# FPGA_Banks_67_68_DDR32.net
KiCad netlist of a schematic drawn in Altium Designer
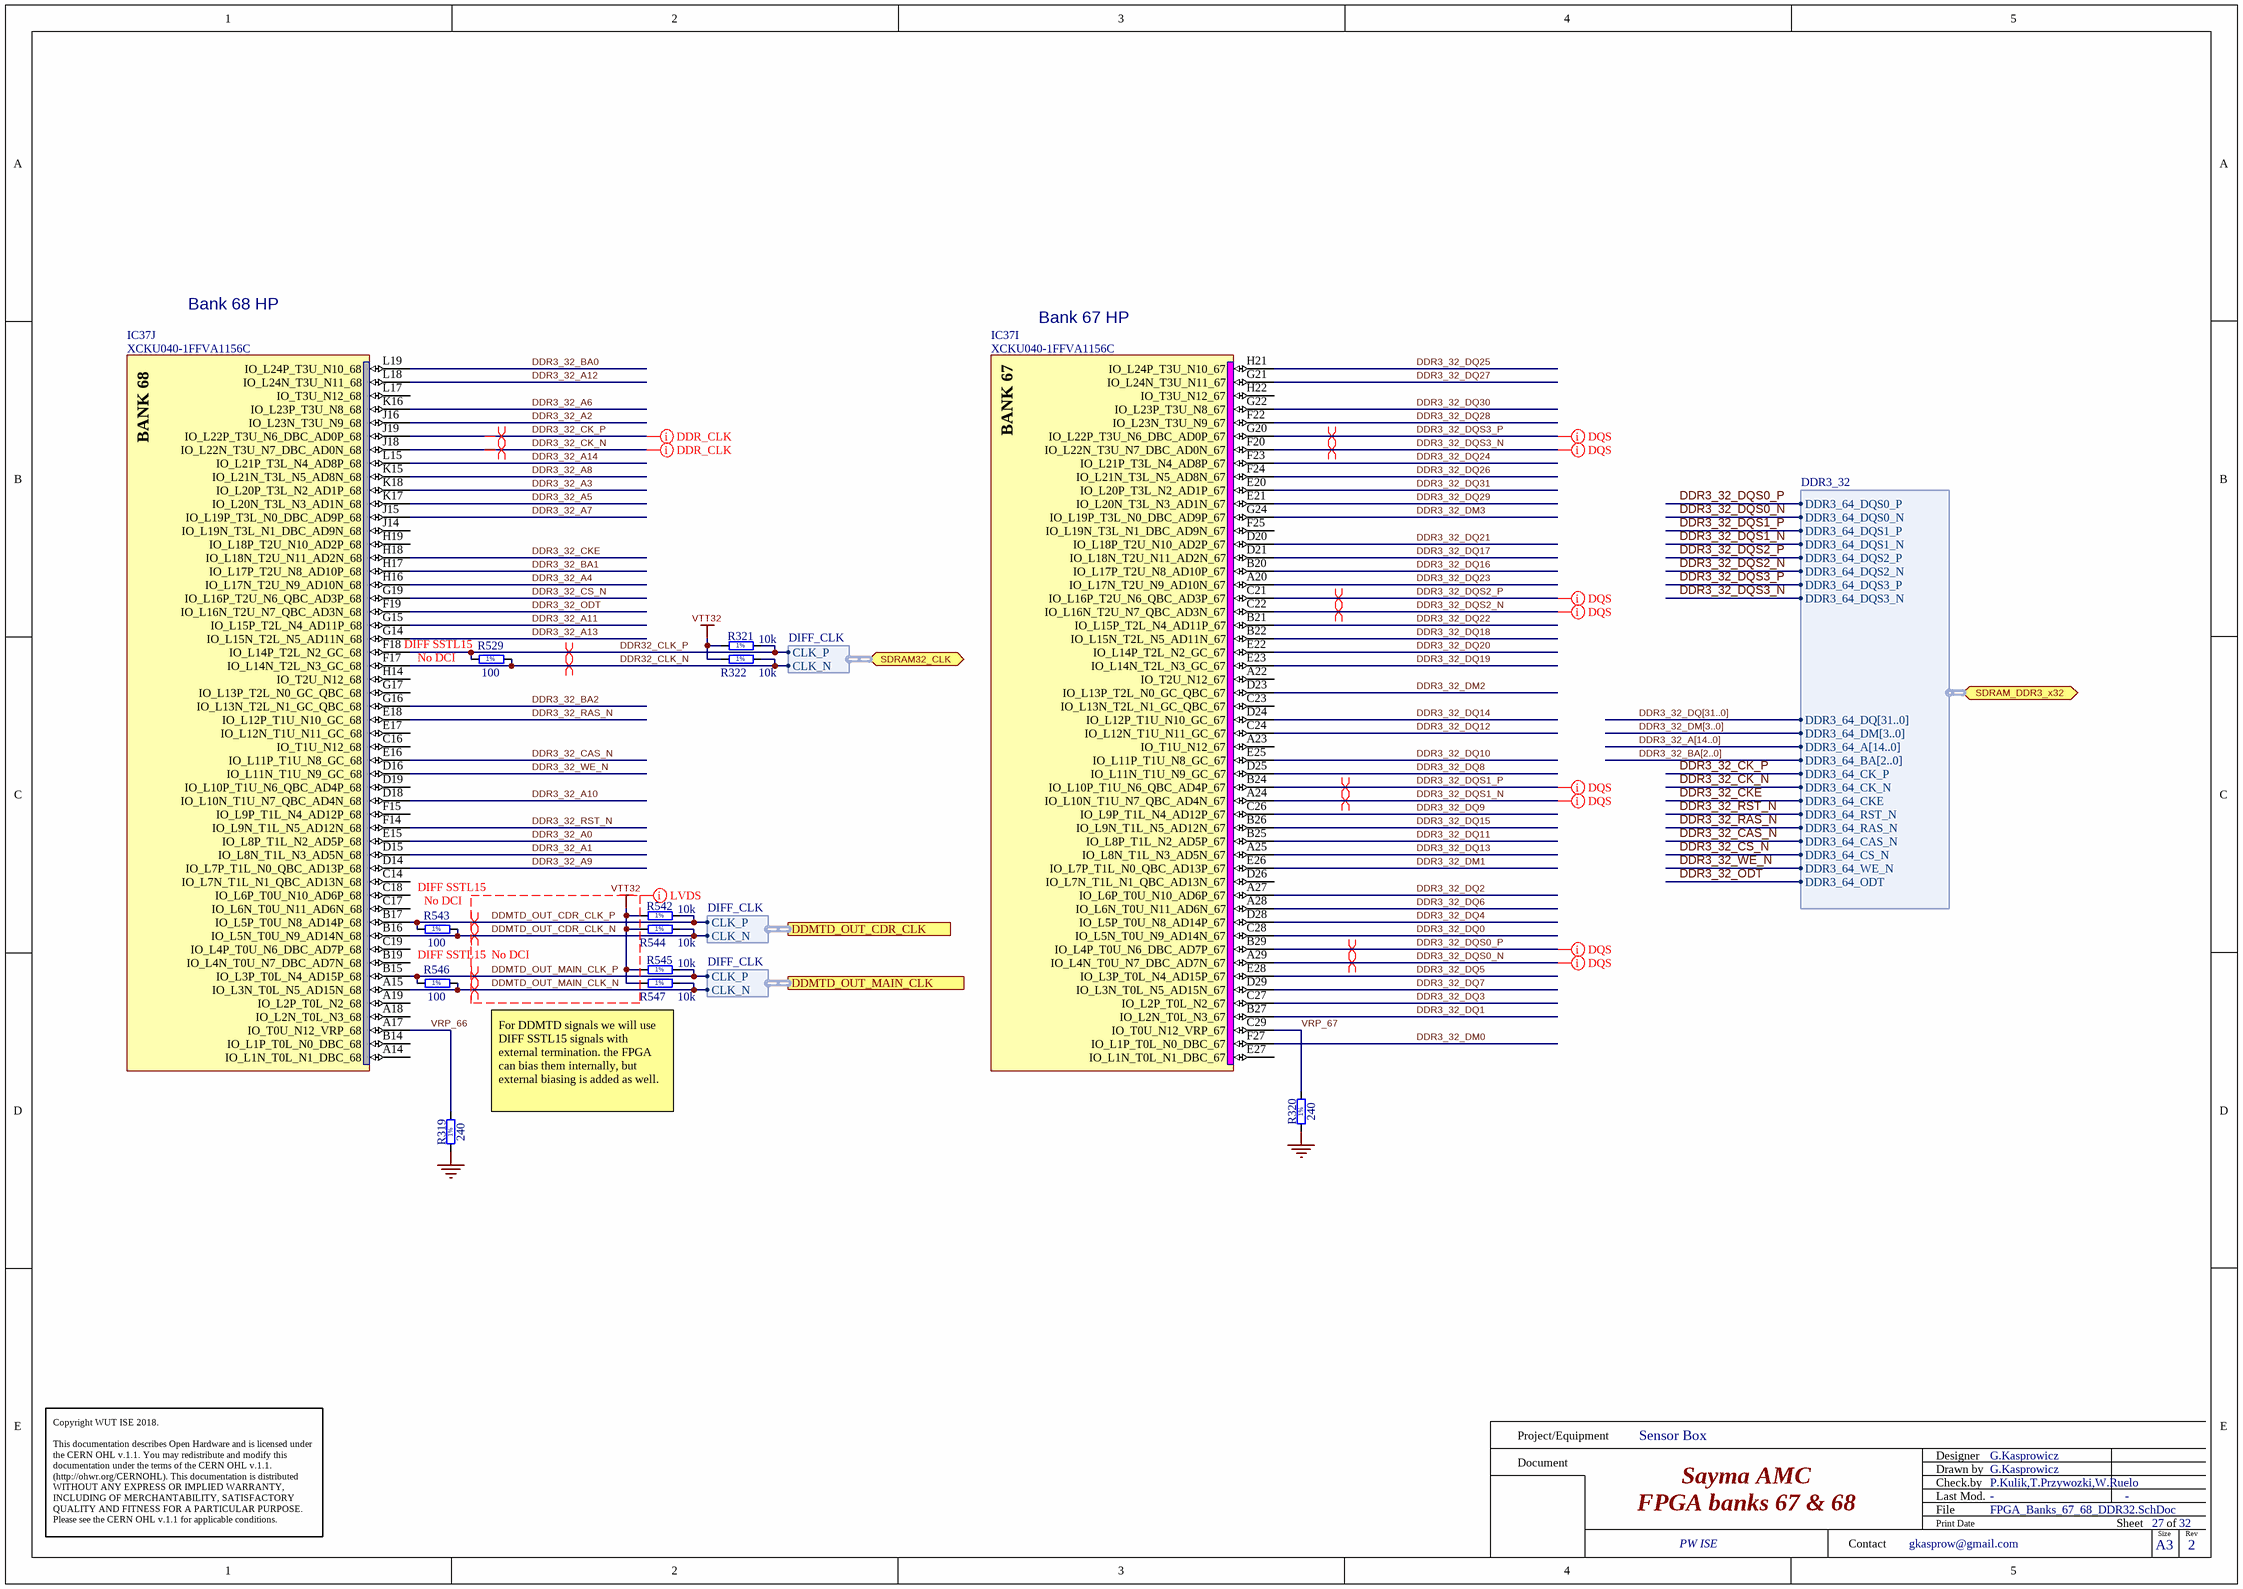
[diagram p0: FPGA_Banks_67_68_DDR32.SchDoc]

(export (version "E")
  (design (tool "Eeschema 10.0.6"))
  (components
    (comp (ref "IC37")
      (value "XCKU040-1FFVA1156C")
      (footprint "BGA1156C100P34X34_3500X3500X350")
      (description "Kintex UltraScale FPGA, 520 I/O, 530K Cells, 1156-Ball BGA, Speed Grade 1, Commercial Grade")
      (fields (field (name "MANUFACTURER") "XILINX") (field (name "AUTHOR") "CERN DEM CA"))
      (libsource (lib "ICs And Semiconductors") (part "XCKU040-1FFVA1156C"))
    )
    (comp (ref "R319")
      (value "240")
      (footprint "RESC1005X40N")
      (description "Resistor - 1%")
      (fields
        (field (name "MANUFACTURER PART NUMBER") "R0402_240R_1%_0.0625W_100PPM")
        (field (name "MANUFACTURER") "GENERIC")
        (field (name "AUTHOR") "CERN DEM JLC")
      )
      (libsource (lib "Resistors") (part "Resistor - 1%"))
    )
    (comp (ref "R320")
      (value "240")
      (footprint "RESC1005X40N")
      (description "Resistor - 1%")
      (fields
        (field (name "MANUFACTURER PART NUMBER") "R0402_240R_1%_0.0625W_100PPM")
        (field (name "MANUFACTURER") "GENERIC")
        (field (name "AUTHOR") "CERN DEM JLC")
      )
      (libsource (lib "Resistors") (part "Resistor - 1%"))
    )
    (comp (ref "R321")
      (value "10k")
      (footprint "RESC1005X40N")
      (description "Resistor - 1%")
      (fields
        (field (name "MANUFACTURER PART NUMBER") "R0402_10K_1%_0.0625W_100PPM")
        (field (name "MANUFACTURER") "GENERIC")
        (field (name "AUTHOR") "CERN DEM JLC")
      )
      (libsource (lib "Resistors") (part "Resistor - 1%"))
    )
    (comp (ref "R322")
      (value "10k")
      (footprint "RESC1005X40N")
      (description "Resistor - 1%")
      (fields
        (field (name "MANUFACTURER PART NUMBER") "R0402_10K_1%_0.0625W_100PPM")
        (field (name "MANUFACTURER") "GENERIC")
        (field (name "AUTHOR") "CERN DEM JLC")
      )
      (libsource (lib "Resistors") (part "Resistor - 1%"))
    )
    (comp (ref "R529")
      (value "100")
      (footprint "RESC0603X28N")
      (description "Resistor - 1%")
      (fields
        (field (name "MANUFACTURER PART NUMBER") "R0201_100R_1%_0.05W_200PPM")
        (field (name "MANUFACTURER") "GENERIC")
        (field (name "AUTHOR") "CERN DEM JLC")
      )
      (libsource (lib "Resistors") (part "Resistor - 1%"))
    )
    (comp (ref "R542")
      (value "10k")
      (footprint "RESC1005X40N")
      (description "Resistor - 1%")
      (fields
        (field (name "MANUFACTURER PART NUMBER") "R0402_10K_1%_0.0625W_100PPM")
        (field (name "MANUFACTURER") "GENERIC")
        (field (name "AUTHOR") "CERN DEM JLC")
      )
      (libsource (lib "Resistors") (part "Resistor - 1%"))
    )
    (comp (ref "R543")
      (value "100")
      (footprint "RESC0603X28N")
      (description "Resistor - 1%")
      (fields
        (field (name "MANUFACTURER PART NUMBER") "R0201_100R_1%_0.05W_200PPM")
        (field (name "MANUFACTURER") "GENERIC")
        (field (name "AUTHOR") "CERN DEM JLC")
      )
      (libsource (lib "Resistors") (part "Resistor - 1%"))
    )
    (comp (ref "R544")
      (value "10k")
      (footprint "RESC1005X40N")
      (description "Resistor - 1%")
      (fields
        (field (name "MANUFACTURER PART NUMBER") "R0402_10K_1%_0.0625W_100PPM")
        (field (name "MANUFACTURER") "GENERIC")
        (field (name "AUTHOR") "CERN DEM JLC")
      )
      (libsource (lib "Resistors") (part "Resistor - 1%"))
    )
    (comp (ref "R545")
      (value "10k")
      (footprint "RESC1005X40N")
      (description "Resistor - 1%")
      (fields
        (field (name "MANUFACTURER PART NUMBER") "R0402_10K_1%_0.0625W_100PPM")
        (field (name "MANUFACTURER") "GENERIC")
        (field (name "AUTHOR") "CERN DEM JLC")
      )
      (libsource (lib "Resistors") (part "Resistor - 1%"))
    )
    (comp (ref "R546")
      (value "100")
      (footprint "RESC0603X28N")
      (description "Resistor - 1%")
      (fields
        (field (name "MANUFACTURER PART NUMBER") "R0201_100R_1%_0.05W_200PPM")
        (field (name "MANUFACTURER") "GENERIC")
        (field (name "AUTHOR") "CERN DEM JLC")
      )
      (libsource (lib "Resistors") (part "Resistor - 1%"))
    )
    (comp (ref "R547")
      (value "10k")
      (footprint "RESC1005X40N")
      (description "Resistor - 1%")
      (fields
        (field (name "MANUFACTURER PART NUMBER") "R0402_10K_1%_0.0625W_100PPM")
        (field (name "MANUFACTURER") "GENERIC")
        (field (name "AUTHOR") "CERN DEM JLC")
      )
      (libsource (lib "Resistors") (part "Resistor - 1%"))
    )
  )
  (nets
    (net (code "3") (name "/DDMTD_OUT_CDR_CLK_N") (class "Default")
      (node (ref "IC37") (pin "B16") (pinfunction "IO_L5N_T0U_N9_AD14N_68_B16") (pintype "bidirectional"))
      (node (ref "R543") (pin "2") (pinfunction "2_2") (pintype "passive"))
      (node (ref "R544") (pin "2") (pinfunction "2_2") (pintype "passive"))
    )
    (net (code "4") (name "/DDMTD_OUT_CDR_CLK_P") (class "Default")
      (node (ref "IC37") (pin "B17") (pinfunction "IO_L5P_T0U_N8_AD14P_68_B17") (pintype "bidirectional"))
      (node (ref "R542") (pin "2") (pinfunction "2_2") (pintype "passive"))
      (node (ref "R543") (pin "1") (pinfunction "1_1") (pintype "passive"))
    )
    (net (code "5") (name "/DDMTD_OUT_MAIN_CLK_N") (class "Default")
      (node (ref "IC37") (pin "A15") (pinfunction "IO_L3N_T0L_N5_AD15N_68_A15") (pintype "bidirectional"))
      (node (ref "R546") (pin "2") (pinfunction "2_2") (pintype "passive"))
      (node (ref "R547") (pin "2") (pinfunction "2_2") (pintype "passive"))
    )
    (net (code "6") (name "/DDMTD_OUT_MAIN_CLK_P") (class "Default")
      (node (ref "IC37") (pin "B15") (pinfunction "IO_L3P_T0L_N4_AD15P_68_B15") (pintype "bidirectional"))
      (node (ref "R545") (pin "2") (pinfunction "2_2") (pintype "passive"))
      (node (ref "R546") (pin "1") (pinfunction "1_1") (pintype "passive"))
    )
    (net (code "7") (name "/DDR3_32_A0") (class "Default")
      (node (ref "IC37") (pin "E15") (pinfunction "IO_L8P_T1L_N2_AD5P_68_E15") (pintype "bidirectional"))
    )
    (net (code "8") (name "/DDR3_32_A1") (class "Default")
      (node (ref "IC37") (pin "D15") (pinfunction "IO_L8N_T1L_N3_AD5N_68_D15") (pintype "bidirectional"))
    )
    (net (code "9") (name "/DDR3_32_A2") (class "Default")
      (node (ref "IC37") (pin "J16") (pinfunction "IO_L23N_T3U_N9_68_J16") (pintype "bidirectional"))
    )
    (net (code "10") (name "/DDR3_32_A3") (class "Default")
      (node (ref "IC37") (pin "K18") (pinfunction "IO_L20P_T3L_N2_AD1P_68_K18") (pintype "bidirectional"))
    )
    (net (code "11") (name "/DDR3_32_A4") (class "Default")
      (node (ref "IC37") (pin "H16") (pinfunction "IO_L17N_T2U_N9_AD10N_68_H16") (pintype "bidirectional"))
    )
    (net (code "12") (name "/DDR3_32_A5") (class "Default")
      (node (ref "IC37") (pin "K17") (pinfunction "IO_L20N_T3L_N3_AD1N_68_K17") (pintype "bidirectional"))
    )
    (net (code "13") (name "/DDR3_32_A6") (class "Default")
      (node (ref "IC37") (pin "K16") (pinfunction "IO_L23P_T3U_N8_68_K16") (pintype "bidirectional"))
    )
    (net (code "14") (name "/DDR3_32_A7") (class "Default")
      (node (ref "IC37") (pin "J15") (pinfunction "IO_L19P_T3L_N0_DBC_AD9P_68_J15") (pintype "bidirectional"))
    )
    (net (code "15") (name "/DDR3_32_A8") (class "Default")
      (node (ref "IC37") (pin "K15") (pinfunction "IO_L21N_T3L_N5_AD8N_68_K15") (pintype "bidirectional"))
    )
    (net (code "16") (name "/DDR3_32_A9") (class "Default")
      (node (ref "IC37") (pin "D14") (pinfunction "IO_L7P_T1L_N0_QBC_AD13P_68_D14") (pintype "bidirectional"))
    )
    (net (code "17") (name "/DDR3_32_A10") (class "Default")
      (node (ref "IC37") (pin "D18") (pinfunction "IO_L10N_T1U_N7_QBC_AD4N_68_D18") (pintype "bidirectional"))
    )
    (net (code "18") (name "/DDR3_32_A11") (class "Default")
      (node (ref "IC37") (pin "G15") (pinfunction "IO_L15P_T2L_N4_AD11P_68_G15") (pintype "bidirectional"))
    )
    (net (code "19") (name "/DDR3_32_A12") (class "Default")
      (node (ref "IC37") (pin "L18") (pinfunction "IO_L24N_T3U_N11_68_L18") (pintype "bidirectional"))
    )
    (net (code "20") (name "/DDR3_32_A13") (class "Default")
      (node (ref "IC37") (pin "G14") (pinfunction "IO_L15N_T2L_N5_AD11N_68_G14") (pintype "bidirectional"))
    )
    (net (code "21") (name "/DDR3_32_A14") (class "Default")
      (node (ref "IC37") (pin "L15") (pinfunction "IO_L21P_T3L_N4_AD8P_68_L15") (pintype "bidirectional"))
    )
    (net (code "23") (name "/DDR3_32_BA0") (class "Default")
      (node (ref "IC37") (pin "L19") (pinfunction "IO_L24P_T3U_N10_68_L19") (pintype "bidirectional"))
    )
    (net (code "24") (name "/DDR3_32_BA1") (class "Default")
      (node (ref "IC37") (pin "H17") (pinfunction "IO_L17P_T2U_N8_AD10P_68_H17") (pintype "bidirectional"))
    )
    (net (code "25") (name "/DDR3_32_BA2") (class "Default")
      (node (ref "IC37") (pin "G16") (pinfunction "IO_L13N_T2L_N1_GC_QBC_68_G16") (pintype "bidirectional"))
    )
    (net (code "27") (name "/DDR3_32_CAS_N") (class "Default")
      (node (ref "IC37") (pin "E16") (pinfunction "IO_L11P_T1U_N8_GC_68_E16") (pintype "bidirectional"))
    )
    (net (code "28") (name "/DDR3_32_CKE") (class "Default")
      (node (ref "IC37") (pin "H18") (pinfunction "IO_L18N_T2U_N11_AD2N_68_H18") (pintype "bidirectional"))
    )
    (net (code "29") (name "/DDR3_32_CK_N") (class "Default")
      (node (ref "IC37") (pin "J18") (pinfunction "IO_L22N_T3U_N7_DBC_AD0N_68_J18") (pintype "bidirectional"))
    )
    (net (code "30") (name "/DDR3_32_CK_P") (class "Default")
      (node (ref "IC37") (pin "J19") (pinfunction "IO_L22P_T3U_N6_DBC_AD0P_68_J19") (pintype "bidirectional"))
    )
    (net (code "31") (name "/DDR3_32_CS_N") (class "Default")
      (node (ref "IC37") (pin "G19") (pinfunction "IO_L16P_T2U_N6_QBC_AD3P_68_G19") (pintype "bidirectional"))
    )
    (net (code "32") (name "/DDR3_32_DM0") (class "Default")
      (node (ref "IC37") (pin "F27") (pinfunction "IO_L1P_T0L_N0_DBC_67_F27") (pintype "bidirectional"))
    )
    (net (code "33") (name "/DDR3_32_DM1") (class "Default")
      (node (ref "IC37") (pin "E26") (pinfunction "IO_L7P_T1L_N0_QBC_AD13P_67_E26") (pintype "bidirectional"))
    )
    (net (code "34") (name "/DDR3_32_DM2") (class "Default")
      (node (ref "IC37") (pin "D23") (pinfunction "IO_L13P_T2L_N0_GC_QBC_67_D23") (pintype "bidirectional"))
    )
    (net (code "35") (name "/DDR3_32_DM3") (class "Default")
      (node (ref "IC37") (pin "G24") (pinfunction "IO_L19P_T3L_N0_DBC_AD9P_67_G24") (pintype "bidirectional"))
    )
    (net (code "37") (name "/DDR3_32_DQ0") (class "Default")
      (node (ref "IC37") (pin "C28") (pinfunction "IO_L5N_T0U_N9_AD14N_67_C28") (pintype "bidirectional"))
    )
    (net (code "38") (name "/DDR3_32_DQ1") (class "Default")
      (node (ref "IC37") (pin "B27") (pinfunction "IO_L2N_T0L_N3_67_B27") (pintype "bidirectional"))
    )
    (net (code "39") (name "/DDR3_32_DQ2") (class "Default")
      (node (ref "IC37") (pin "A27") (pinfunction "IO_L6P_T0U_N10_AD6P_67_A27") (pintype "bidirectional"))
    )
    (net (code "40") (name "/DDR3_32_DQ3") (class "Default")
      (node (ref "IC37") (pin "C27") (pinfunction "IO_L2P_T0L_N2_67_C27") (pintype "bidirectional"))
    )
    (net (code "41") (name "/DDR3_32_DQ4") (class "Default")
      (node (ref "IC37") (pin "D28") (pinfunction "IO_L5P_T0U_N8_AD14P_67_D28") (pintype "bidirectional"))
    )
    (net (code "42") (name "/DDR3_32_DQ5") (class "Default")
      (node (ref "IC37") (pin "E28") (pinfunction "IO_L3P_T0L_N4_AD15P_67_E28") (pintype "bidirectional"))
    )
    (net (code "43") (name "/DDR3_32_DQ6") (class "Default")
      (node (ref "IC37") (pin "A28") (pinfunction "IO_L6N_T0U_N11_AD6N_67_A28") (pintype "bidirectional"))
    )
    (net (code "44") (name "/DDR3_32_DQ7") (class "Default")
      (node (ref "IC37") (pin "D29") (pinfunction "IO_L3N_T0L_N5_AD15N_67_D29") (pintype "bidirectional"))
    )
    (net (code "45") (name "/DDR3_32_DQ8") (class "Default")
      (node (ref "IC37") (pin "D25") (pinfunction "IO_L11N_T1U_N9_GC_67_D25") (pintype "bidirectional"))
    )
    (net (code "46") (name "/DDR3_32_DQ9") (class "Default")
      (node (ref "IC37") (pin "C26") (pinfunction "IO_L9P_T1L_N4_AD12P_67_C26") (pintype "bidirectional"))
    )
    (net (code "47") (name "/DDR3_32_DQ10") (class "Default")
      (node (ref "IC37") (pin "E25") (pinfunction "IO_L11P_T1U_N8_GC_67_E25") (pintype "bidirectional"))
    )
    (net (code "48") (name "/DDR3_32_DQ11") (class "Default")
      (node (ref "IC37") (pin "B25") (pinfunction "IO_L8P_T1L_N2_AD5P_67_B25") (pintype "bidirectional"))
    )
    (net (code "49") (name "/DDR3_32_DQ12") (class "Default")
      (node (ref "IC37") (pin "C24") (pinfunction "IO_L12N_T1U_N11_GC_67_C24") (pintype "bidirectional"))
    )
    (net (code "50") (name "/DDR3_32_DQ13") (class "Default")
      (node (ref "IC37") (pin "A25") (pinfunction "IO_L8N_T1L_N3_AD5N_67_A25") (pintype "bidirectional"))
    )
    (net (code "51") (name "/DDR3_32_DQ14") (class "Default")
      (node (ref "IC37") (pin "D24") (pinfunction "IO_L12P_T1U_N10_GC_67_D24") (pintype "bidirectional"))
    )
    (net (code "52") (name "/DDR3_32_DQ15") (class "Default")
      (node (ref "IC37") (pin "B26") (pinfunction "IO_L9N_T1L_N5_AD12N_67_B26") (pintype "bidirectional"))
    )
    (net (code "53") (name "/DDR3_32_DQ16") (class "Default")
      (node (ref "IC37") (pin "B20") (pinfunction "IO_L17P_T2U_N8_AD10P_67_B20") (pintype "bidirectional"))
    )
    (net (code "54") (name "/DDR3_32_DQ17") (class "Default")
      (node (ref "IC37") (pin "D21") (pinfunction "IO_L18N_T2U_N11_AD2N_67_D21") (pintype "bidirectional"))
    )
    (net (code "55") (name "/DDR3_32_DQ18") (class "Default")
      (node (ref "IC37") (pin "B22") (pinfunction "IO_L15N_T2L_N5_AD11N_67_B22") (pintype "bidirectional"))
    )
    (net (code "56") (name "/DDR3_32_DQ19") (class "Default")
      (node (ref "IC37") (pin "E23") (pinfunction "IO_L14N_T2L_N3_GC_67_E23") (pintype "bidirectional"))
    )
    (net (code "57") (name "/DDR3_32_DQ20") (class "Default")
      (node (ref "IC37") (pin "E22") (pinfunction "IO_L14P_T2L_N2_GC_67_E22") (pintype "bidirectional"))
    )
    (net (code "58") (name "/DDR3_32_DQ21") (class "Default")
      (node (ref "IC37") (pin "D20") (pinfunction "IO_L18P_T2U_N10_AD2P_67_D20") (pintype "bidirectional"))
    )
    (net (code "59") (name "/DDR3_32_DQ22") (class "Default")
      (node (ref "IC37") (pin "B21") (pinfunction "IO_L15P_T2L_N4_AD11P_67_B21") (pintype "bidirectional"))
    )
    (net (code "60") (name "/DDR3_32_DQ23") (class "Default")
      (node (ref "IC37") (pin "A20") (pinfunction "IO_L17N_T2U_N9_AD10N_67_A20") (pintype "bidirectional"))
    )
    (net (code "61") (name "/DDR3_32_DQ24") (class "Default")
      (node (ref "IC37") (pin "F23") (pinfunction "IO_L21P_T3L_N4_AD8P_67_F23") (pintype "bidirectional"))
    )
    (net (code "62") (name "/DDR3_32_DQ25") (class "Default")
      (node (ref "IC37") (pin "H21") (pinfunction "IO_L24P_T3U_N10_67_H21") (pintype "bidirectional"))
    )
    (net (code "63") (name "/DDR3_32_DQ26") (class "Default")
      (node (ref "IC37") (pin "F24") (pinfunction "IO_L21N_T3L_N5_AD8N_67_F24") (pintype "bidirectional"))
    )
    (net (code "64") (name "/DDR3_32_DQ27") (class "Default")
      (node (ref "IC37") (pin "G21") (pinfunction "IO_L24N_T3U_N11_67_G21") (pintype "bidirectional"))
    )
    (net (code "65") (name "/DDR3_32_DQ28") (class "Default")
      (node (ref "IC37") (pin "F22") (pinfunction "IO_L23N_T3U_N9_67_F22") (pintype "bidirectional"))
    )
    (net (code "66") (name "/DDR3_32_DQ29") (class "Default")
      (node (ref "IC37") (pin "E21") (pinfunction "IO_L20N_T3L_N3_AD1N_67_E21") (pintype "bidirectional"))
    )
    (net (code "67") (name "/DDR3_32_DQ30") (class "Default")
      (node (ref "IC37") (pin "G22") (pinfunction "IO_L23P_T3U_N8_67_G22") (pintype "bidirectional"))
    )
    (net (code "68") (name "/DDR3_32_DQ31") (class "Default")
      (node (ref "IC37") (pin "E20") (pinfunction "IO_L20P_T3L_N2_AD1P_67_E20") (pintype "bidirectional"))
    )
    (net (code "69") (name "/DDR3_32_DQS0_N") (class "Default")
      (node (ref "IC37") (pin "A29") (pinfunction "IO_L4N_T0U_N7_DBC_AD7N_67_A29") (pintype "bidirectional"))
    )
    (net (code "70") (name "/DDR3_32_DQS0_P") (class "Default")
      (node (ref "IC37") (pin "B29") (pinfunction "IO_L4P_T0U_N6_DBC_AD7P_67_B29") (pintype "bidirectional"))
    )
    (net (code "71") (name "/DDR3_32_DQS1_N") (class "Default")
      (node (ref "IC37") (pin "A24") (pinfunction "IO_L10N_T1U_N7_QBC_AD4N_67_A24") (pintype "bidirectional"))
    )
    (net (code "72") (name "/DDR3_32_DQS1_P") (class "Default")
      (node (ref "IC37") (pin "B24") (pinfunction "IO_L10P_T1U_N6_QBC_AD4P_67_B24") (pintype "bidirectional"))
    )
    (net (code "73") (name "/DDR3_32_DQS2_N") (class "Default")
      (node (ref "IC37") (pin "C22") (pinfunction "IO_L16N_T2U_N7_QBC_AD3N_67_C22") (pintype "bidirectional"))
    )
    (net (code "74") (name "/DDR3_32_DQS2_P") (class "Default")
      (node (ref "IC37") (pin "C21") (pinfunction "IO_L16P_T2U_N6_QBC_AD3P_67_C21") (pintype "bidirectional"))
    )
    (net (code "75") (name "/DDR3_32_DQS3_N") (class "Default")
      (node (ref "IC37") (pin "F20") (pinfunction "IO_L22N_T3U_N7_DBC_AD0N_67_F20") (pintype "bidirectional"))
    )
    (net (code "76") (name "/DDR3_32_DQS3_P") (class "Default")
      (node (ref "IC37") (pin "G20") (pinfunction "IO_L22P_T3U_N6_DBC_AD0P_67_G20") (pintype "bidirectional"))
    )
    (net (code "78") (name "/DDR3_32_ODT") (class "Default")
      (node (ref "IC37") (pin "F19") (pinfunction "IO_L16N_T2U_N7_QBC_AD3N_68_F19") (pintype "bidirectional"))
    )
    (net (code "79") (name "/DDR3_32_RAS_N") (class "Default")
      (node (ref "IC37") (pin "E18") (pinfunction "IO_L12P_T1U_N10_GC_68_E18") (pintype "bidirectional"))
    )
    (net (code "80") (name "/DDR3_32_RST_N") (class "Default")
      (node (ref "IC37") (pin "F14") (pinfunction "IO_L9N_T1L_N5_AD12N_68_F14") (pintype "bidirectional"))
    )
    (net (code "81") (name "/DDR3_32_WE_N") (class "Default")
      (node (ref "IC37") (pin "D16") (pinfunction "IO_L11N_T1U_N9_GC_68_D16") (pintype "bidirectional"))
    )
    (net (code "82") (name "/DDR32_CLK_N") (class "Default")
      (node (ref "IC37") (pin "F17") (pinfunction "IO_L14N_T2L_N3_GC_68_F17") (pintype "bidirectional"))
      (node (ref "R322") (pin "2") (pinfunction "2_2") (pintype "passive"))
      (node (ref "R529") (pin "2") (pinfunction "2_2") (pintype "passive"))
    )
    (net (code "83") (name "/DDR32_CLK_P") (class "Default")
      (node (ref "IC37") (pin "F18") (pinfunction "IO_L14P_T2L_N2_GC_68_F18") (pintype "bidirectional"))
      (node (ref "R321") (pin "2") (pinfunction "2_2") (pintype "passive"))
      (node (ref "R529") (pin "1") (pinfunction "1_1") (pintype "passive"))
    )
    (net (code "84") (name "/VRP_66") (class "Default")
      (node (ref "IC37") (pin "A17") (pinfunction "IO_T0U_N12_VRP_68_A17") (pintype "bidirectional"))
      (node (ref "R319") (pin "2") (pinfunction "2_2") (pintype "passive"))
    )
    (net (code "85") (name "/VRP_67") (class "Default")
      (node (ref "IC37") (pin "C29") (pinfunction "IO_T0U_N12_VRP_67_C29") (pintype "bidirectional"))
      (node (ref "R320") (pin "2") (pinfunction "2_2") (pintype "passive"))
    )
    (net (code "88") (name "GND") (class "Default")
      (node (ref "R319") (pin "1") (pinfunction "1_1") (pintype "passive"))
      (node (ref "R320") (pin "1") (pinfunction "1_1") (pintype "passive"))
    )
    (net (code "89") (name "VTT32") (class "Default")
      (node (ref "R321") (pin "1") (pinfunction "1_1") (pintype "passive"))
      (node (ref "R322") (pin "1") (pinfunction "1_1") (pintype "passive"))
      (node (ref "R542") (pin "1") (pinfunction "1_1") (pintype "passive"))
      (node (ref "R544") (pin "1") (pinfunction "1_1") (pintype "passive"))
      (node (ref "R545") (pin "1") (pinfunction "1_1") (pintype "passive"))
      (node (ref "R547") (pin "1") (pinfunction "1_1") (pintype "passive"))
    )
    (net (code "90") (name "unconnected-(IC37I-IO_L1N_T0L_N1_DBC_67-PadE27)") (class "Default")
      (node (ref "IC37") (pin "E27") (pinfunction "IO_L1N_T0L_N1_DBC_67_E27") (pintype "bidirectional"))
    )
    (net (code "91") (name "unconnected-(IC37I-IO_L7N_T1L_N1_QBC_AD13N_67-PadD26)") (class "Default")
      (node (ref "IC37") (pin "D26") (pinfunction "IO_L7N_T1L_N1_QBC_AD13N_67_D26") (pintype "bidirectional"))
    )
    (net (code "92") (name "unconnected-(IC37I-IO_L13N_T2L_N1_GC_QBC_67-PadC23)") (class "Default")
      (node (ref "IC37") (pin "C23") (pinfunction "IO_L13N_T2L_N1_GC_QBC_67_C23") (pintype "bidirectional"))
    )
    (net (code "93") (name "unconnected-(IC37I-IO_L19N_T3L_N1_DBC_AD9N_67-PadF25)") (class "Default")
      (node (ref "IC37") (pin "F25") (pinfunction "IO_L19N_T3L_N1_DBC_AD9N_67_F25") (pintype "bidirectional"))
    )
    (net (code "94") (name "unconnected-(IC37I-IO_T1U_N12_67-PadA23)") (class "Default")
      (node (ref "IC37") (pin "A23") (pinfunction "IO_T1U_N12_67_A23") (pintype "bidirectional"))
    )
    (net (code "95") (name "unconnected-(IC37I-IO_T2U_N12_67-PadA22)") (class "Default")
      (node (ref "IC37") (pin "A22") (pinfunction "IO_T2U_N12_67_A22") (pintype "bidirectional"))
    )
    (net (code "96") (name "unconnected-(IC37I-IO_T3U_N12_67-PadH22)") (class "Default")
      (node (ref "IC37") (pin "H22") (pinfunction "IO_T3U_N12_67_H22") (pintype "bidirectional"))
    )
    (net (code "97") (name "unconnected-(IC37J-IO_L1N_T0L_N1_DBC_68-PadA14)") (class "Default")
      (node (ref "IC37") (pin "A14") (pinfunction "IO_L1N_T0L_N1_DBC_68_A14") (pintype "bidirectional"))
    )
    (net (code "98") (name "unconnected-(IC37J-IO_L1P_T0L_N0_DBC_68-PadB14)") (class "Default")
      (node (ref "IC37") (pin "B14") (pinfunction "IO_L1P_T0L_N0_DBC_68_B14") (pintype "bidirectional"))
    )
    (net (code "99") (name "unconnected-(IC37J-IO_L2N_T0L_N3_68-PadA18)") (class "Default")
      (node (ref "IC37") (pin "A18") (pinfunction "IO_L2N_T0L_N3_68_A18") (pintype "bidirectional"))
    )
    (net (code "100") (name "unconnected-(IC37J-IO_L2P_T0L_N2_68-PadA19)") (class "Default")
      (node (ref "IC37") (pin "A19") (pinfunction "IO_L2P_T0L_N2_68_A19") (pintype "bidirectional"))
    )
    (net (code "101") (name "unconnected-(IC37J-IO_L4N_T0U_N7_DBC_AD7N_68-PadB19)") (class "Default")
      (node (ref "IC37") (pin "B19") (pinfunction "IO_L4N_T0U_N7_DBC_AD7N_68_B19") (pintype "bidirectional"))
    )
    (net (code "102") (name "unconnected-(IC37J-IO_L4P_T0U_N6_DBC_AD7P_68-PadC19)") (class "Default")
      (node (ref "IC37") (pin "C19") (pinfunction "IO_L4P_T0U_N6_DBC_AD7P_68_C19") (pintype "bidirectional"))
    )
    (net (code "103") (name "unconnected-(IC37J-IO_L6N_T0U_N11_AD6N_68-PadC17)") (class "Default")
      (node (ref "IC37") (pin "C17") (pinfunction "IO_L6N_T0U_N11_AD6N_68_C17") (pintype "bidirectional"))
    )
    (net (code "104") (name "unconnected-(IC37J-IO_L6P_T0U_N10_AD6P_68-PadC18)") (class "Default")
      (node (ref "IC37") (pin "C18") (pinfunction "IO_L6P_T0U_N10_AD6P_68_C18") (pintype "bidirectional"))
    )
    (net (code "105") (name "unconnected-(IC37J-IO_L7N_T1L_N1_QBC_AD13N_68-PadC14)") (class "Default")
      (node (ref "IC37") (pin "C14") (pinfunction "IO_L7N_T1L_N1_QBC_AD13N_68_C14") (pintype "bidirectional"))
    )
    (net (code "106") (name "unconnected-(IC37J-IO_L9P_T1L_N4_AD12P_68-PadF15)") (class "Default")
      (node (ref "IC37") (pin "F15") (pinfunction "IO_L9P_T1L_N4_AD12P_68_F15") (pintype "bidirectional"))
    )
    (net (code "107") (name "unconnected-(IC37J-IO_L10P_T1U_N6_QBC_AD4P_68-PadD19)") (class "Default")
      (node (ref "IC37") (pin "D19") (pinfunction "IO_L10P_T1U_N6_QBC_AD4P_68_D19") (pintype "bidirectional"))
    )
    (net (code "108") (name "unconnected-(IC37J-IO_L12N_T1U_N11_GC_68-PadE17)") (class "Default")
      (node (ref "IC37") (pin "E17") (pinfunction "IO_L12N_T1U_N11_GC_68_E17") (pintype "bidirectional"))
    )
    (net (code "109") (name "unconnected-(IC37J-IO_L13P_T2L_N0_GC_QBC_68-PadG17)") (class "Default")
      (node (ref "IC37") (pin "G17") (pinfunction "IO_L13P_T2L_N0_GC_QBC_68_G17") (pintype "bidirectional"))
    )
    (net (code "110") (name "unconnected-(IC37J-IO_L18P_T2U_N10_AD2P_68-PadH19)") (class "Default")
      (node (ref "IC37") (pin "H19") (pinfunction "IO_L18P_T2U_N10_AD2P_68_H19") (pintype "bidirectional"))
    )
    (net (code "111") (name "unconnected-(IC37J-IO_L19N_T3L_N1_DBC_AD9N_68-PadJ14)") (class "Default")
      (node (ref "IC37") (pin "J14") (pinfunction "IO_L19N_T3L_N1_DBC_AD9N_68_J14") (pintype "bidirectional"))
    )
    (net (code "112") (name "unconnected-(IC37J-IO_T1U_N12_68-PadC16)") (class "Default")
      (node (ref "IC37") (pin "C16") (pinfunction "IO_T1U_N12_68_C16") (pintype "bidirectional"))
    )
    (net (code "113") (name "unconnected-(IC37J-IO_T2U_N12_68-PadH14)") (class "Default")
      (node (ref "IC37") (pin "H14") (pinfunction "IO_T2U_N12_68_H14") (pintype "bidirectional"))
    )
    (net (code "114") (name "unconnected-(IC37J-IO_T3U_N12_68-PadL17)") (class "Default")
      (node (ref "IC37") (pin "L17") (pinfunction "IO_T3U_N12_68_L17") (pintype "bidirectional"))
    )
  )
)
